# PG02_PPG.net
KiCad netlist of a schematic drawn in Altium Designer
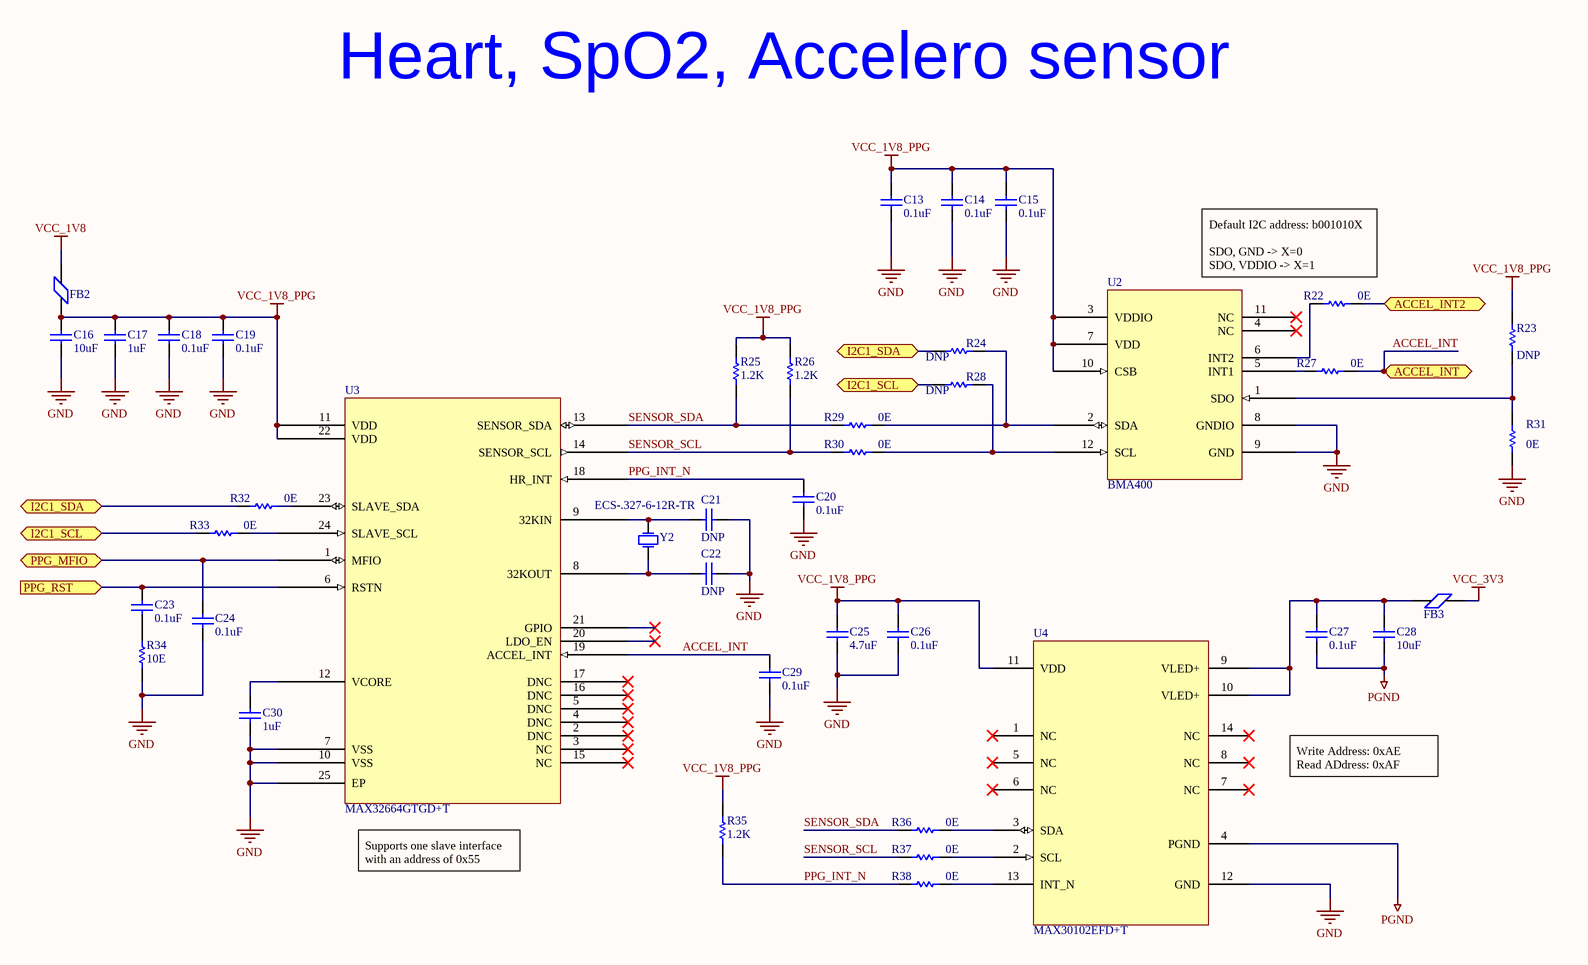
[diagram p0: PG02_PPG.SchDoc]

(export (version "E")
  (design (tool "Eeschema 10.0.6"))
  (components
    (comp (ref "C13")
      (value "0.1uF")
      (footprint "0402C")
      (description "CAP CER 0.1UF 50V X7R 0402")
      (libsource (lib "Smart Ring Components") (part "CAP_0402_0.1uF_50V"))
    )
    (comp (ref "C14")
      (value "0.1uF")
      (footprint "0402C")
      (description "CAP CER 0.1UF 50V X7R 0402")
      (libsource (lib "Smart Ring Components") (part "CAP_0402_0.1uF_50V"))
    )
    (comp (ref "C15")
      (value "0.1uF")
      (footprint "0402C")
      (description "CAP CER 0.1UF 50V X7R 0402")
      (libsource (lib "Smart Ring Components") (part "CAP_0402_0.1uF_50V"))
    )
    (comp (ref "C16")
      (value "10uF")
      (footprint "0805C")
      (description "CAP CER 10UF 16V X7R 0805")
      (libsource (lib "Smart Ring Components") (part "CAP_0805_10uF_16V"))
    )
    (comp (ref "C17")
      (value "1uF")
      (footprint "0805C")
      (description "CAP CER 1UF 25V X7R 0805")
      (libsource (lib "Smart Ring Components") (part "CAP_0805_1uF_25V"))
    )
    (comp (ref "C18")
      (value "0.1uF")
      (footprint "0402C")
      (description "CAP CER 0.1UF 50V X7R 0402")
      (libsource (lib "Smart Ring Components") (part "CAP_0402_0.1uF_50V"))
    )
    (comp (ref "C19")
      (value "0.1uF")
      (footprint "0402C")
      (description "CAP CER 0.1UF 50V X7R 0402")
      (libsource (lib "Smart Ring Components") (part "CAP_0402_0.1uF_50V"))
    )
    (comp (ref "C20")
      (value "0.1uF")
      (footprint "0402C")
      (description "CAP CER 0.1UF 50V X7R 0402")
      (libsource (lib "Smart Ring Components") (part "CAP_0402_0.1uF_50V"))
    )
    (comp (ref "C21")
      (value "DNP")
      (footprint "0402C")
      (description "CAP CER DNP 0402")
      (fields (field (name "MFR") "Generic"))
      (libsource (lib "Smart Ring Components") (part "CAP_0402_DNP"))
    )
    (comp (ref "C22")
      (value "DNP")
      (footprint "0402C")
      (description "CAP CER DNP 0402")
      (fields (field (name "MFR") "Generic"))
      (libsource (lib "Smart Ring Components") (part "CAP_0402_DNP"))
    )
    (comp (ref "C23")
      (value "0.1uF")
      (footprint "0402C")
      (description "CAP CER 0.1UF 50V X7R 0402")
      (libsource (lib "Smart Ring Components") (part "CAP_0402_0.1uF_50V"))
    )
    (comp (ref "C24")
      (value "0.1uF")
      (footprint "0402C")
      (description "CAP CER 0.1UF 50V X7R 0402")
      (libsource (lib "Smart Ring Components") (part "CAP_0402_0.1uF_50V"))
    )
    (comp (ref "C25")
      (value "4.7uF")
      (footprint "0805C")
      (description "CAP CER MLCC 4.7uF X7R 16V  0805")
      (libsource (lib "Smart Ring Components") (part "CAP_0805_4.7uF_16V"))
    )
    (comp (ref "C26")
      (value "0.1uF")
      (footprint "0402C")
      (description "CAP CER 0.1UF 50V X7R 0402")
      (libsource (lib "Smart Ring Components") (part "CAP_0402_0.1uF_50V"))
    )
    (comp (ref "C27")
      (value "0.1uF")
      (footprint "0402C")
      (description "CAP CER 0.1UF 50V X7R 0402")
      (libsource (lib "Smart Ring Components") (part "CAP_0402_0.1uF_50V"))
    )
    (comp (ref "C28")
      (value "10uF")
      (footprint "0805C")
      (description "CAP CER 10UF 16V X7R 0805")
      (libsource (lib "Smart Ring Components") (part "CAP_0805_10uF_16V"))
    )
    (comp (ref "C29")
      (value "0.1uF")
      (footprint "0402C")
      (description "CAP CER 0.1UF 50V X7R 0402")
      (libsource (lib "Smart Ring Components") (part "CAP_0402_0.1uF_50V"))
    )
    (comp (ref "C30")
      (value "1uF")
      (footprint "0805C")
      (description "CAP CER 1UF 25V X7R 0805")
      (libsource (lib "Smart Ring Components") (part "CAP_0805_1uF_25V"))
    )
    (comp (ref "FB2")
      (value "Ferrite Bead")
      (footprint "0402R")
      (description "CHIP BEAD 600 OHM 0402 300mA")
      (fields (field (name "MFR") "Walsin") (field (name "MPN") "WLBD1005K2U601TP"))
      (libsource (lib "Smart Ring Components") (part "Ferrite Bead"))
    )
    (comp (ref "FB3")
      (value "Ferrite Bead")
      (footprint "0402R")
      (description "CHIP BEAD 600 OHM 0402 300mA")
      (fields (field (name "MFR") "Walsin") (field (name "MPN") "WLBD1005K2U601TP"))
      (libsource (lib "Smart Ring Components") (part "Ferrite Bead"))
    )
    (comp (ref "R22")
      (value "0E")
      (footprint "0402R")
      (description "RES 0 OHM JUMPER 1/16W 0402")
      (fields (field (name "MFR") "Generic"))
      (libsource (lib "Smart Ring Components") (part "RES_0402_0E"))
    )
    (comp (ref "R23")
      (value "DNP")
      (footprint "0402C")
      (description "RES DNP 0402")
      (libsource (lib "Smart Ring Components") (part "RES_0402_DNP"))
    )
    (comp (ref "R24")
      (value "DNP")
      (footprint "0402C")
      (description "RES DNP 0402")
      (libsource (lib "Smart Ring Components") (part "RES_0402_DNP"))
    )
    (comp (ref "R25")
      (value "1.2K")
      (footprint "0402R")
      (description "RES 1.2K OHM 1% 1/16W 0402")
      (fields (field (name "MFR") "Generic"))
      (libsource (lib "Smart Ring Components") (part "RES_0402_1.2k"))
    )
    (comp (ref "R26")
      (value "1.2K")
      (footprint "0402R")
      (description "RES 1.2K OHM 1% 1/16W 0402")
      (fields (field (name "MFR") "Generic"))
      (libsource (lib "Smart Ring Components") (part "RES_0402_1.2k"))
    )
    (comp (ref "R27")
      (value "0E")
      (footprint "0402R")
      (description "RES 0 OHM JUMPER 1/16W 0402")
      (fields (field (name "MFR") "Generic"))
      (libsource (lib "Smart Ring Components") (part "RES_0402_0E"))
    )
    (comp (ref "R28")
      (value "DNP")
      (footprint "0402C")
      (description "RES DNP 0402")
      (libsource (lib "Smart Ring Components") (part "RES_0402_DNP"))
    )
    (comp (ref "R29")
      (value "0E")
      (footprint "0402R")
      (description "RES 0 OHM JUMPER 1/16W 0402")
      (fields (field (name "MFR") "Generic"))
      (libsource (lib "Smart Ring Components") (part "RES_0402_0E"))
    )
    (comp (ref "R30")
      (value "0E")
      (footprint "0402R")
      (description "RES 0 OHM JUMPER 1/16W 0402")
      (fields (field (name "MFR") "Generic"))
      (libsource (lib "Smart Ring Components") (part "RES_0402_0E"))
    )
    (comp (ref "R31")
      (value "0E")
      (footprint "0402R")
      (description "RES 0 OHM JUMPER 1/16W 0402")
      (fields (field (name "MFR") "Generic"))
      (libsource (lib "Smart Ring Components") (part "RES_0402_0E"))
    )
    (comp (ref "R32")
      (value "0E")
      (footprint "0402R")
      (description "RES 0 OHM JUMPER 1/16W 0402")
      (fields (field (name "MFR") "Generic"))
      (libsource (lib "Smart Ring Components") (part "RES_0402_0E"))
    )
    (comp (ref "R33")
      (value "0E")
      (footprint "0402R")
      (description "RES 0 OHM JUMPER 1/16W 0402")
      (fields (field (name "MFR") "Generic"))
      (libsource (lib "Smart Ring Components") (part "RES_0402_0E"))
    )
    (comp (ref "R34")
      (value "10E")
      (footprint "0402R")
      (description "RES 10 OHM 1% 1/16W 0402")
      (fields (field (name "MFR") "Generic"))
      (libsource (lib "Smart Ring Components") (part "RES_0402_10E"))
    )
    (comp (ref "R35")
      (value "1.2K")
      (footprint "0402R")
      (description "RES 1.2K OHM 1% 1/16W 0402")
      (fields (field (name "MFR") "Generic"))
      (libsource (lib "Smart Ring Components") (part "RES_0402_1.2k"))
    )
    (comp (ref "R36")
      (value "0E")
      (footprint "0402R")
      (description "RES 0 OHM JUMPER 1/16W 0402")
      (fields (field (name "MFR") "Generic"))
      (libsource (lib "Smart Ring Components") (part "RES_0402_0E"))
    )
    (comp (ref "R37")
      (value "0E")
      (footprint "0402R")
      (description "RES 0 OHM JUMPER 1/16W 0402")
      (fields (field (name "MFR") "Generic"))
      (libsource (lib "Smart Ring Components") (part "RES_0402_0E"))
    )
    (comp (ref "R38")
      (value "0E")
      (footprint "0402R")
      (description "RES 0 OHM JUMPER 1/16W 0402")
      (fields (field (name "MFR") "Generic"))
      (libsource (lib "Smart Ring Components") (part "RES_0402_0E"))
    )
    (comp (ref "U2")
      (value "BMA400")
      (footprint "BMA400")
      (description "ACCELEROMETER 2-16G 12LGA")
      (fields (field (name "MFR") "Bosch") (field (name "MPN") "BMA400"))
      (libsource (lib "Smart Ring Components") (part "AccSensor_BMA400"))
    )
    (comp (ref "U3")
      (value "MAX32664GTGD+T")
      (footprint "MAX32664GTGA+T")
      (description "Biometric Sensors CORTEX M4F 96MHZ ME11, TQFN 3X3")
      (fields (field (name "MFR") "Maxim Integrated") (field (name "MPN") "MAX32664GTGD+T"))
      (libsource (lib "Smart Ring Components") (part "MAX32664GTGD+T"))
    )
    (comp (ref "U4")
      (value "MAX30102EFD+T")
      (footprint "MAX30101EFD+T")
      (description "Biometric Sensors Oximeter/Heart Rate Integrated Optical Sensor")
      (fields (field (name "MFR") "Maxim Integrated"))
      (libsource (lib "Smart Ring Components") (part "MAX30101EFD+T"))
    )
    (comp (ref "Y2")
      (value "ECS-.327-6-12R-TR")
      (footprint "ECS-.327-6-12R-TR")
      (description "CRYSTAL 32.7680KHZ 6PF SMD")
      (fields (field (name "MFR") "ECS Inc."))
      (libsource (lib "Smart Ring Components") (part "XTAL_32.768kHz"))
    )
  )
  (nets
    (net (code "1") (name "/ACCEL_INT") (class "Default")
      (node (ref "C29") (pin "2") (pinfunction "2_2") (pintype "passive"))
      (node (ref "R27") (pin "2") (pinfunction "2_2") (pintype "passive"))
      (node (ref "U3") (pin "19") (pinfunction "ACCEL_INT_19") (pintype "input"))
    )
    (net (code "2") (name "/ACCEL_INT2") (class "Default")
      (node (ref "R22") (pin "2") (pinfunction "2_2") (pintype "passive"))
    )
    (net (code "3") (name "/I2C1_SCL") (class "Default")
      (node (ref "R28") (pin "2") (pinfunction "2_2") (pintype "passive"))
      (node (ref "R33") (pin "1") (pinfunction "1_1") (pintype "passive"))
    )
    (net (code "4") (name "/I2C1_SDA") (class "Default")
      (node (ref "R24") (pin "2") (pinfunction "2_2") (pintype "passive"))
      (node (ref "R32") (pin "1") (pinfunction "1_1") (pintype "passive"))
    )
    (net (code "5") (name "/PPG_INT_N") (class "Default")
      (node (ref "C20") (pin "2") (pinfunction "2_2") (pintype "passive"))
      (node (ref "R35") (pin "1") (pinfunction "1_1") (pintype "passive"))
      (node (ref "R38") (pin "1") (pinfunction "1_1") (pintype "passive"))
      (node (ref "U3") (pin "18") (pinfunction "HR_INT_18") (pintype "input"))
    )
    (net (code "6") (name "/PPG_MFIO") (class "Default")
      (node (ref "C24") (pin "2") (pinfunction "2_2") (pintype "passive"))
      (node (ref "U3") (pin "1") (pinfunction "MFIO_1") (pintype "bidirectional"))
    )
    (net (code "7") (name "/PPG_RST") (class "Default")
      (node (ref "C23") (pin "2") (pinfunction "2_2") (pintype "passive"))
      (node (ref "U3") (pin "6") (pinfunction "RSTN_6") (pintype "input"))
    )
    (net (code "8") (name "/SENSOR_SCL") (class "Default")
      (node (ref "R26") (pin "1") (pinfunction "1_1") (pintype "passive"))
      (node (ref "R30") (pin "1") (pinfunction "1_1") (pintype "passive"))
      (node (ref "R37") (pin "1") (pinfunction "1_1") (pintype "passive"))
      (node (ref "U3") (pin "14") (pinfunction "SENSOR_SCL_14") (pintype "output"))
    )
    (net (code "9") (name "/SENSOR_SDA") (class "Default")
      (node (ref "R25") (pin "1") (pinfunction "1_1") (pintype "passive"))
      (node (ref "R29") (pin "1") (pinfunction "1_1") (pintype "passive"))
      (node (ref "R36") (pin "1") (pinfunction "1_1") (pintype "passive"))
      (node (ref "U3") (pin "13") (pinfunction "SENSOR_SDA_13") (pintype "bidirectional"))
    )
    (net (code "10") (name "GND") (class "Default")
      (node (ref "C13") (pin "1") (pinfunction "1_1") (pintype "passive"))
      (node (ref "C14") (pin "1") (pinfunction "1_1") (pintype "passive"))
      (node (ref "C15") (pin "1") (pinfunction "1_1") (pintype "passive"))
      (node (ref "C16") (pin "1") (pinfunction "1_1") (pintype "passive"))
      (node (ref "C17") (pin "1") (pinfunction "1_1") (pintype "passive"))
      (node (ref "C18") (pin "1") (pinfunction "1_1") (pintype "passive"))
      (node (ref "C19") (pin "1") (pinfunction "1_1") (pintype "passive"))
      (node (ref "C20") (pin "1") (pinfunction "1_1") (pintype "passive"))
      (node (ref "C21") (pin "1") (pinfunction "1_1") (pintype "passive"))
      (node (ref "C22") (pin "1") (pinfunction "1_1") (pintype "passive"))
      (node (ref "C24") (pin "1") (pinfunction "1_1") (pintype "passive"))
      (node (ref "C25") (pin "1") (pinfunction "1_1") (pintype "passive"))
      (node (ref "C26") (pin "1") (pinfunction "1_1") (pintype "passive"))
      (node (ref "C29") (pin "1") (pinfunction "1_1") (pintype "passive"))
      (node (ref "C30") (pin "1") (pinfunction "1_1") (pintype "passive"))
      (node (ref "R31") (pin "1") (pinfunction "1_1") (pintype "passive"))
      (node (ref "R34") (pin "1") (pinfunction "1_1") (pintype "passive"))
      (node (ref "U2") (pin "8") (pinfunction "GNDIO_8") (pintype "power_in"))
      (node (ref "U2") (pin "9") (pinfunction "GND_9") (pintype "power_in"))
      (node (ref "U3") (pin "10") (pinfunction "VSS_10") (pintype "power_in"))
      (node (ref "U3") (pin "25") (pinfunction "EP_25") (pintype "power_in"))
      (node (ref "U3") (pin "7") (pinfunction "VSS_7") (pintype "power_in"))
      (node (ref "U4") (pin "12") (pinfunction "GND_12") (pintype "power_in"))
    )
    (net (code "11") (name "Net-(C23-Pad1)") (class "Default")
      (node (ref "C23") (pin "1") (pinfunction "1_1") (pintype "passive"))
      (node (ref "R34") (pin "2") (pinfunction "2_2") (pintype "passive"))
    )
    (net (code "12") (name "Net-(C27-Pad2)") (class "Default")
      (node (ref "C27") (pin "2") (pinfunction "2_2") (pintype "passive"))
      (node (ref "C28") (pin "2") (pinfunction "2_2") (pintype "passive"))
      (node (ref "FB3") (pin "1") (pinfunction "VREF_1") (pintype "passive"))
      (node (ref "U4") (pin "10") (pinfunction "VLED+_10") (pintype "power_in"))
      (node (ref "U4") (pin "9") (pinfunction "VLED+_9") (pintype "power_in"))
    )
    (net (code "13") (name "Net-(U2-INT1)") (class "Default")
      (node (ref "R27") (pin "1") (pinfunction "1_1") (pintype "passive"))
      (node (ref "U2") (pin "5") (pinfunction "INT1_5") (pintype "passive"))
    )
    (net (code "14") (name "Net-(U2-INT2)") (class "Default")
      (node (ref "R22") (pin "1") (pinfunction "1_1") (pintype "passive"))
      (node (ref "U2") (pin "6") (pinfunction "INT2_6") (pintype "passive"))
    )
    (net (code "15") (name "Net-(U2-SCL)") (class "Default")
      (node (ref "R28") (pin "1") (pinfunction "1_1") (pintype "passive"))
      (node (ref "R30") (pin "2") (pinfunction "2_2") (pintype "passive"))
      (node (ref "U2") (pin "12") (pinfunction "SCL_12") (pintype "input"))
    )
    (net (code "16") (name "Net-(U2-SDA)") (class "Default")
      (node (ref "R24") (pin "1") (pinfunction "1_1") (pintype "passive"))
      (node (ref "R29") (pin "2") (pinfunction "2_2") (pintype "passive"))
      (node (ref "U2") (pin "2") (pinfunction "SDA_2") (pintype "bidirectional"))
    )
    (net (code "17") (name "Net-(U2-SDO)") (class "Default")
      (node (ref "R23") (pin "1") (pinfunction "1_1") (pintype "passive"))
      (node (ref "R31") (pin "2") (pinfunction "2_2") (pintype "passive"))
      (node (ref "U2") (pin "1") (pinfunction "SDO_1") (pintype "input"))
    )
    (net (code "18") (name "Net-(U3-32KIN)") (class "Default")
      (node (ref "C21") (pin "2") (pinfunction "2_2") (pintype "passive"))
      (node (ref "U3") (pin "9") (pinfunction "32KIN_9") (pintype "passive"))
      (node (ref "Y2") (pin "2") (pinfunction "OSC2_2") (pintype "passive"))
    )
    (net (code "19") (name "Net-(U3-32KOUT)") (class "Default")
      (node (ref "C22") (pin "2") (pinfunction "2_2") (pintype "passive"))
      (node (ref "U3") (pin "8") (pinfunction "32KOUT_8") (pintype "passive"))
      (node (ref "Y2") (pin "1") (pinfunction "OSC1_1") (pintype "passive"))
    )
    (net (code "20") (name "Net-(U3-SLAVE_SCL)") (class "Default")
      (node (ref "R33") (pin "2") (pinfunction "2_2") (pintype "passive"))
      (node (ref "U3") (pin "24") (pinfunction "SLAVE_SCL_24") (pintype "input"))
    )
    (net (code "21") (name "Net-(U3-SLAVE_SDA)") (class "Default")
      (node (ref "R32") (pin "2") (pinfunction "2_2") (pintype "passive"))
      (node (ref "U3") (pin "23") (pinfunction "SLAVE_SDA_23") (pintype "bidirectional"))
    )
    (net (code "22") (name "Net-(U3-VCORE)") (class "Default")
      (node (ref "C30") (pin "2") (pinfunction "2_2") (pintype "passive"))
      (node (ref "U3") (pin "12") (pinfunction "VCORE_12") (pintype "power_in"))
    )
    (net (code "23") (name "Net-(U4-INT_N)") (class "Default")
      (node (ref "R38") (pin "2") (pinfunction "2_2") (pintype "passive"))
      (node (ref "U4") (pin "13") (pinfunction "INT_N_13") (pintype "passive"))
    )
    (net (code "24") (name "Net-(U4-SCL)") (class "Default")
      (node (ref "R37") (pin "2") (pinfunction "2_2") (pintype "passive"))
      (node (ref "U4") (pin "2") (pinfunction "SCL_2") (pintype "input"))
    )
    (net (code "25") (name "Net-(U4-SDA)") (class "Default")
      (node (ref "R36") (pin "2") (pinfunction "2_2") (pintype "passive"))
      (node (ref "U4") (pin "3") (pinfunction "SDA_3") (pintype "bidirectional"))
    )
    (net (code "26") (name "PGND") (class "Default")
      (node (ref "C27") (pin "1") (pinfunction "1_1") (pintype "passive"))
      (node (ref "C28") (pin "1") (pinfunction "1_1") (pintype "passive"))
      (node (ref "U4") (pin "4") (pinfunction "PGND_4") (pintype "power_in"))
    )
    (net (code "27") (name "VCC_1V8") (class "Default")
      (node (ref "FB2") (pin "2") (pinfunction "VREF_2") (pintype "passive"))
    )
    (net (code "28") (name "VCC_1V8_PPG") (class "Default")
      (node (ref "C13") (pin "2") (pinfunction "2_2") (pintype "passive"))
      (node (ref "C14") (pin "2") (pinfunction "2_2") (pintype "passive"))
      (node (ref "C15") (pin "2") (pinfunction "2_2") (pintype "passive"))
      (node (ref "C16") (pin "2") (pinfunction "2_2") (pintype "passive"))
      (node (ref "C17") (pin "2") (pinfunction "2_2") (pintype "passive"))
      (node (ref "C18") (pin "2") (pinfunction "2_2") (pintype "passive"))
      (node (ref "C19") (pin "2") (pinfunction "2_2") (pintype "passive"))
      (node (ref "C25") (pin "2") (pinfunction "2_2") (pintype "passive"))
      (node (ref "C26") (pin "2") (pinfunction "2_2") (pintype "passive"))
      (node (ref "FB2") (pin "1") (pinfunction "VREF_1") (pintype "passive"))
      (node (ref "R23") (pin "2") (pinfunction "2_2") (pintype "passive"))
      (node (ref "R25") (pin "2") (pinfunction "2_2") (pintype "passive"))
      (node (ref "R26") (pin "2") (pinfunction "2_2") (pintype "passive"))
      (node (ref "R35") (pin "2") (pinfunction "2_2") (pintype "passive"))
      (node (ref "U2") (pin "10") (pinfunction "CSB_10") (pintype "input"))
      (node (ref "U2") (pin "3") (pinfunction "VDDIO_3") (pintype "power_in"))
      (node (ref "U2") (pin "7") (pinfunction "VDD_7") (pintype "power_in"))
      (node (ref "U3") (pin "11") (pinfunction "VDD_11") (pintype "power_in"))
      (node (ref "U3") (pin "22") (pinfunction "VDD_22") (pintype "power_in"))
      (node (ref "U4") (pin "11") (pinfunction "VDD_11") (pintype "power_in"))
    )
    (net (code "29") (name "VCC_3V3") (class "Default")
      (node (ref "FB3") (pin "2") (pinfunction "VREF_2") (pintype "passive"))
    )
    (net (code "30") (name "unconnected-(U2-NC-Pad4)") (class "Default")
      (node (ref "U2") (pin "4") (pinfunction "NC_4") (pintype "passive+no_connect"))
    )
    (net (code "31") (name "unconnected-(U2-NC-Pad11)") (class "Default")
      (node (ref "U2") (pin "11") (pinfunction "NC_11") (pintype "passive+no_connect"))
    )
    (net (code "32") (name "unconnected-(U3-DNC-Pad2)") (class "Default")
      (node (ref "U3") (pin "2") (pinfunction "DNC_2") (pintype "passive+no_connect"))
    )
    (net (code "33") (name "unconnected-(U3-DNC-Pad4)") (class "Default")
      (node (ref "U3") (pin "4") (pinfunction "DNC_4") (pintype "passive+no_connect"))
    )
    (net (code "34") (name "unconnected-(U3-DNC-Pad5)") (class "Default")
      (node (ref "U3") (pin "5") (pinfunction "DNC_5") (pintype "passive+no_connect"))
    )
    (net (code "35") (name "unconnected-(U3-DNC-Pad16)") (class "Default")
      (node (ref "U3") (pin "16") (pinfunction "DNC_16") (pintype "passive+no_connect"))
    )
    (net (code "36") (name "unconnected-(U3-DNC-Pad17)") (class "Default")
      (node (ref "U3") (pin "17") (pinfunction "DNC_17") (pintype "passive+no_connect"))
    )
    (net (code "37") (name "unconnected-(U3-GPIO-Pad21)") (class "Default")
      (node (ref "U3") (pin "21") (pinfunction "GPIO_21") (pintype "passive+no_connect"))
    )
    (net (code "38") (name "unconnected-(U3-LDO_EN-Pad20)") (class "Default")
      (node (ref "U3") (pin "20") (pinfunction "LDO_EN_20") (pintype "passive+no_connect"))
    )
    (net (code "39") (name "unconnected-(U3-NC-Pad3)") (class "Default")
      (node (ref "U3") (pin "3") (pinfunction "NC_3") (pintype "passive+no_connect"))
    )
    (net (code "40") (name "unconnected-(U3-NC-Pad15)") (class "Default")
      (node (ref "U3") (pin "15") (pinfunction "NC_15") (pintype "passive+no_connect"))
    )
    (net (code "41") (name "unconnected-(U4-NC-Pad1)") (class "Default")
      (node (ref "U4") (pin "1") (pinfunction "NC_1") (pintype "passive+no_connect"))
    )
    (net (code "42") (name "unconnected-(U4-NC-Pad5)") (class "Default")
      (node (ref "U4") (pin "5") (pinfunction "NC_5") (pintype "passive+no_connect"))
    )
    (net (code "43") (name "unconnected-(U4-NC-Pad6)") (class "Default")
      (node (ref "U4") (pin "6") (pinfunction "NC_6") (pintype "passive+no_connect"))
    )
    (net (code "44") (name "unconnected-(U4-NC-Pad7)") (class "Default")
      (node (ref "U4") (pin "7") (pinfunction "NC_7") (pintype "passive+no_connect"))
    )
    (net (code "45") (name "unconnected-(U4-NC-Pad8)") (class "Default")
      (node (ref "U4") (pin "8") (pinfunction "NC_8") (pintype "passive+no_connect"))
    )
    (net (code "46") (name "unconnected-(U4-NC-Pad14)") (class "Default")
      (node (ref "U4") (pin "14") (pinfunction "NC_14") (pintype "passive+no_connect"))
    )
  )
)
